# mcu.net
KiCad netlist of a schematic drawn in Altium Designer
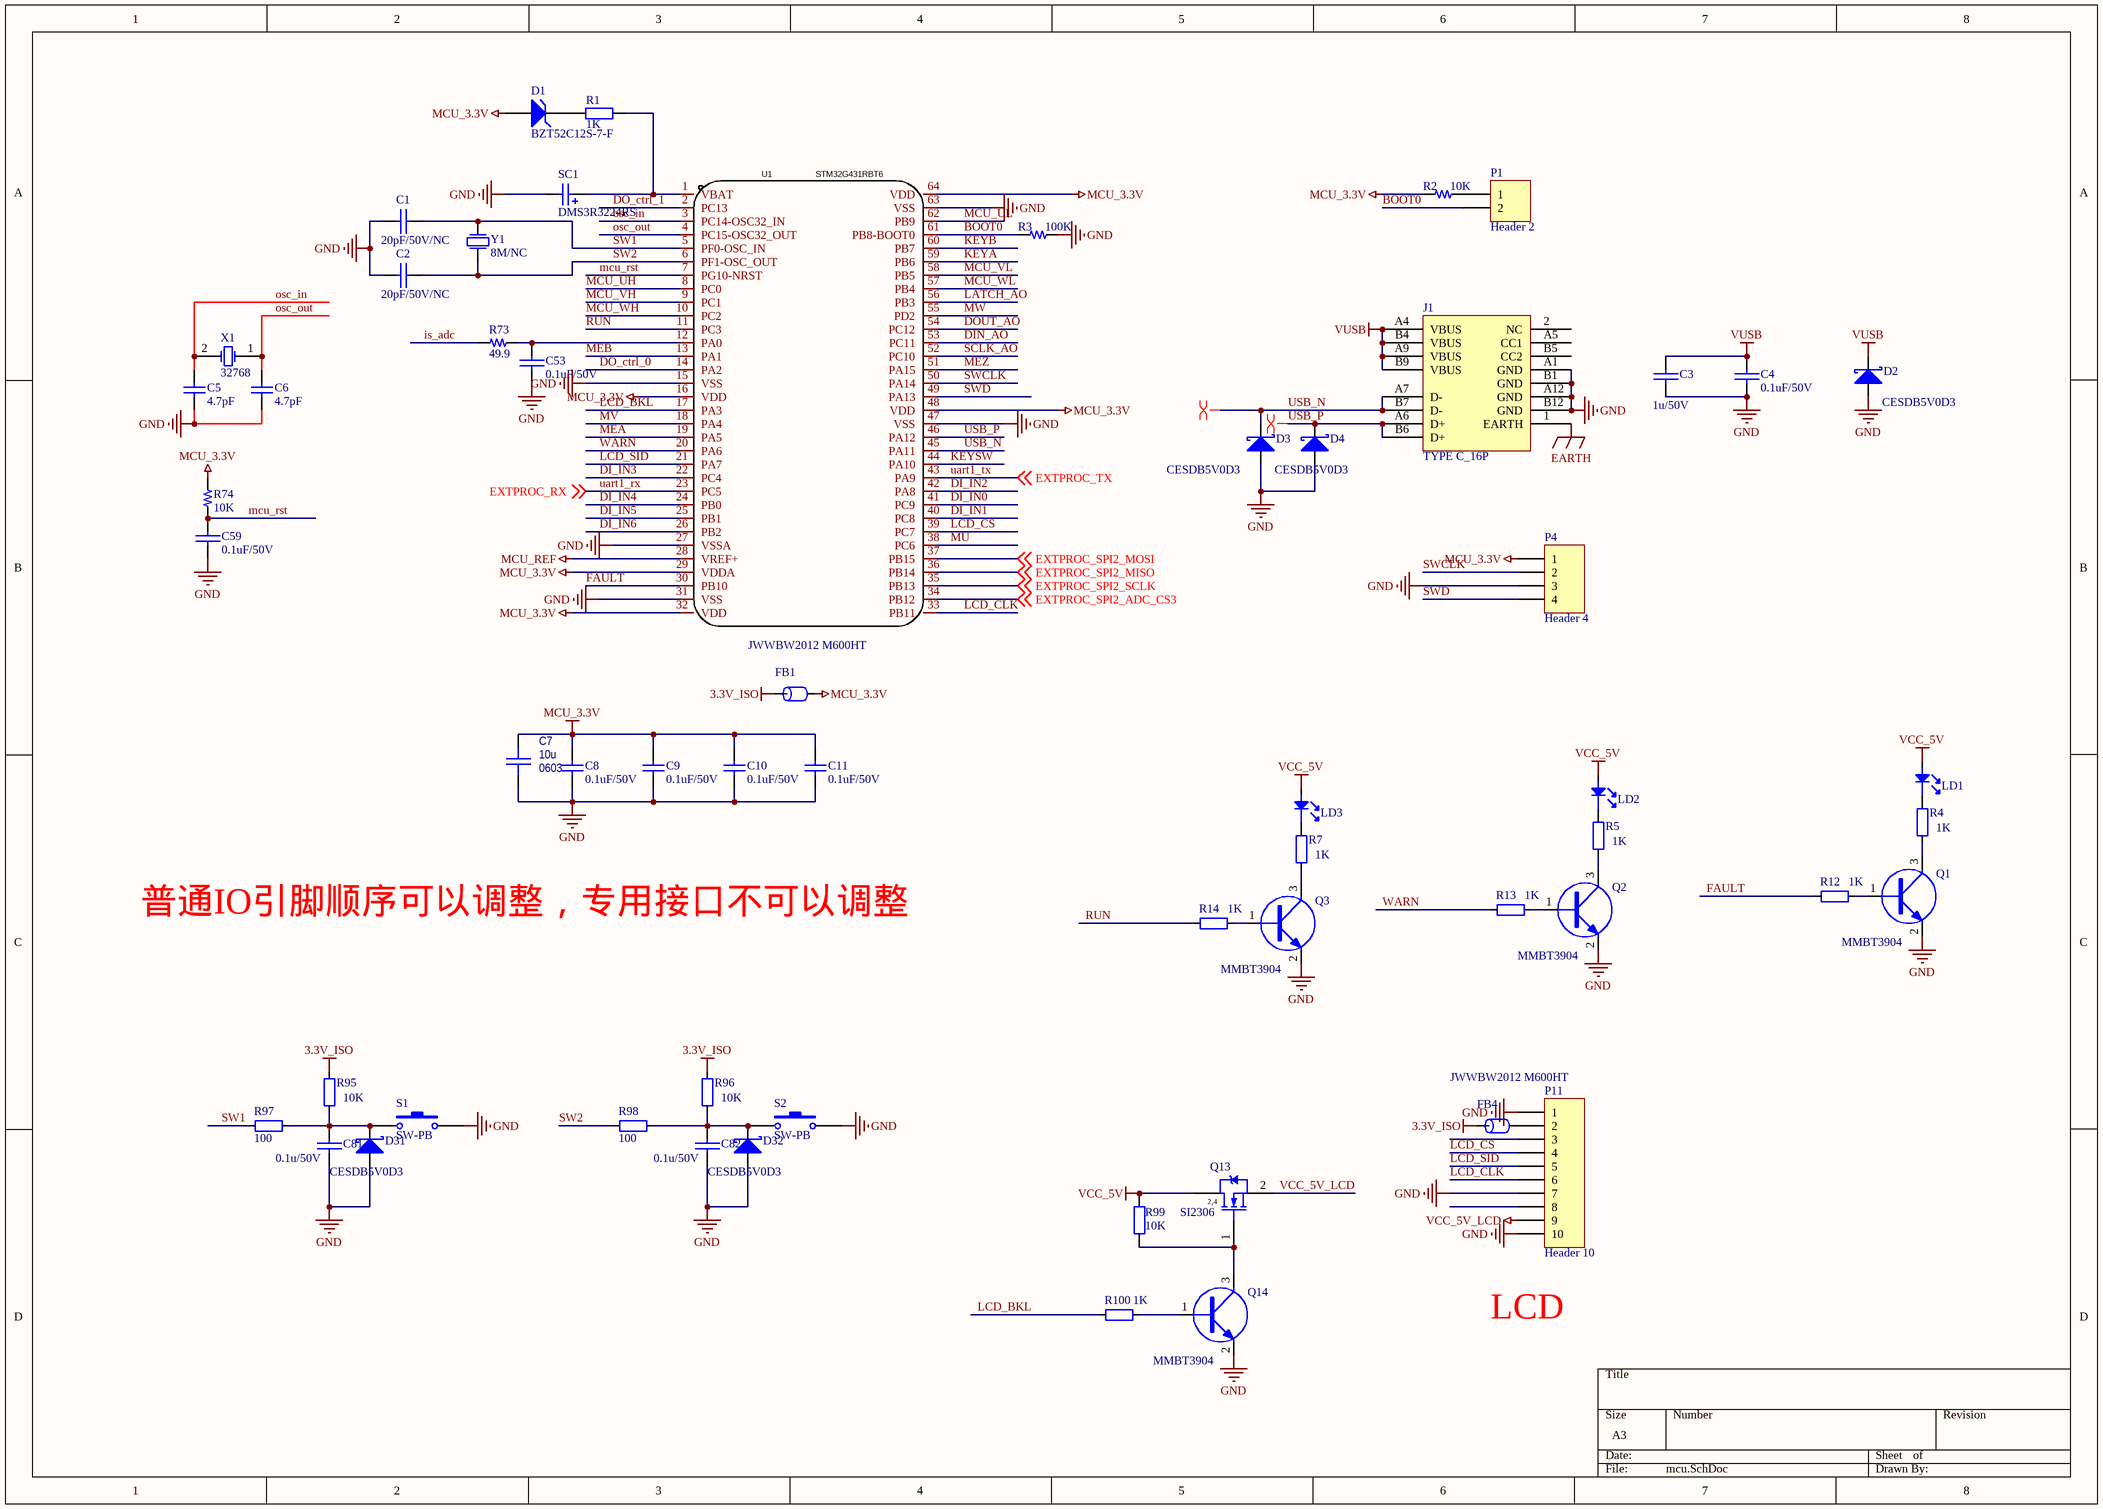
[diagram p0: mcu.SchDoc]

(export (version "E")
  (design (tool "Eeschema 10.0.6"))
  (components
    (comp (ref "C1")
      (value "20pF/50V/NC")
      (footprint "0603C")
      (fields (field (name "Comment") "20pF/25V/NC"))
      (libsource (lib "SM") (part "CAP"))
    )
    (comp (ref "C2")
      (value "20pF/50V/NC")
      (footprint "0603C")
      (fields (field (name "Comment") "20pF/25V/NC"))
      (libsource (lib "SM") (part "CAP"))
    )
    (comp (ref "C3")
      (value "1u/50V")
      (footprint "0603C")
      (fields (field (name "Comment") "1uF/25V"))
      (libsource (lib "SM") (part "CAP"))
    )
    (comp (ref "C4") (value "0.1uF/50V") (footprint "0603C") (libsource (lib "SM") (part "CAP")))
    (comp (ref "C5")
      (value "4.7pF")
      (footprint "0603C")
      (description "Capacitor")
      (fields (field (name "PUBLISHER") "Altium Limited"))
      (libsource (lib "Miscellaneous Devices") (part "Cap"))
    )
    (comp (ref "C6")
      (value "4.7pF")
      (footprint "0603C")
      (description "Capacitor")
      (fields (field (name "PUBLISHER") "Altium Limited"))
      (libsource (lib "Miscellaneous Devices") (part "Cap"))
    )
    (comp (ref "C7")
      (value "10u")
      (footprint "CAPC1608X092N_0603")
      (description "Capacitor, MLCC")
      (fields
        (field (name "MANUFACTURER") "Murata Electronics")
        (field (name "PARTNUMBER") "GRM188R61A106KE69D")
        (field (name "PACKAGE") "0603")
      )
      (libsource (lib "Karl") (part "Capacitor_0603"))
    )
    (comp (ref "C8")
      (value "0.1uF/50V")
      (footprint "0603C")
      (description "Capacitor")
      (fields (field (name "PUBLISHER") "Altium Limited"))
      (libsource (lib "Miscellaneous Devices") (part "Cap"))
    )
    (comp (ref "C9")
      (value "0.1uF/50V")
      (footprint "0603C")
      (description "Capacitor")
      (fields (field (name "PUBLISHER") "Altium Limited"))
      (libsource (lib "Miscellaneous Devices") (part "Cap"))
    )
    (comp (ref "C10")
      (value "0.1uF/50V")
      (footprint "0603C")
      (description "Capacitor")
      (fields (field (name "PUBLISHER") "Altium Limited"))
      (libsource (lib "Miscellaneous Devices") (part "Cap"))
    )
    (comp (ref "C11")
      (value "0.1uF/50V")
      (footprint "0603C")
      (description "Capacitor")
      (fields (field (name "PUBLISHER") "Altium Limited"))
      (libsource (lib "Miscellaneous Devices") (part "Cap"))
    )
    (comp (ref "C53") (value "0.1uF/50V") (footprint "0603C") (libsource (lib "SM") (part "CAP")))
    (comp (ref "C59") (value "0.1uF/50V") (footprint "0603C") (libsource (lib "SM") (part "CAP")))
    (comp (ref "C81")
      (value "0.1u/50V")
      (footprint "0603C")
      (fields (field (name "Comment") "1uF/25V"))
      (libsource (lib "SM") (part "CAP"))
    )
    (comp (ref "C82")
      (value "0.1u/50V")
      (footprint "0603C")
      (fields (field (name "Comment") "1uF/25V"))
      (libsource (lib "SM") (part "CAP"))
    )
    (comp (ref "D1")
      (value "BZT52C12S-7-F")
      (footprint "DIOD-SOD323-2_V")
      (libsource (lib "Bogen") (part "BZT52C12S-7-F"))
    )
    (comp (ref "D2") (value "CESDB5V0D3") (footprint "SOD323") (libsource (lib "*") (part "DIODE S")))
    (comp (ref "D3") (value "CESDB5V0D3") (footprint "SOD323") (libsource (lib "*") (part "DIODE S")))
    (comp (ref "D4") (value "CESDB5V0D3") (footprint "SOD323") (libsource (lib "*") (part "DIODE S")))
    (comp (ref "D31") (value "CESDB5V0D3") (footprint "SOD323") (libsource (lib "*") (part "DIODE S")))
    (comp (ref "D32") (value "CESDB5V0D3") (footprint "SOD323") (libsource (lib "*") (part "DIODE S")))
    (comp (ref "FB1")
      (value "JWWBW2012 M600HT")
      (footprint "0805R")
      (libsource (lib "Schlib_20110825") (part "FB"))
    )
    (comp (ref "FB4")
      (value "JWWBW2012 M600HT")
      (footprint "0805R")
      (libsource (lib "Schlib_20110825") (part "FB"))
    )
    (comp (ref "J1")
      (value "TYPE C_16P")
      (footprint "TYPEC_16P")
      (libsource (lib "Schlib_20110825") (part "TYPE C_16P"))
    )
    (comp (ref "LD1")
      (value "LED_Green_19-217")
      (footprint "0603led")
      (libsource (lib "RC_M_D_00") (part "LED_Green_19-217"))
    )
    (comp (ref "LD2")
      (value "LED_Green_19-217")
      (footprint "0603led")
      (libsource (lib "RC_M_D_00") (part "LED_Green_19-217"))
    )
    (comp (ref "LD3")
      (value "LED_Green_19-217")
      (footprint "0603led")
      (libsource (lib "RC_M_D_00") (part "LED_Green_19-217"))
    )
    (comp (ref "P1")
      (value "Header 2")
      (footprint "HDR1X2")
      (fields (field (name "PUBLISHER") "Altium Limited"))
      (libsource (lib "Miscellaneous Connectors") (part "Header 2"))
    )
    (comp (ref "P4")
      (value "Header 4")
      (footprint "HDR1X4")
      (fields (field (name "PUBLISHER") "Altium Limited"))
      (libsource (lib "Miscellaneous Connectors") (part "Header 4"))
    )
    (comp (ref "P11")
      (value "Header 10")
      (footprint "HDR1X10")
      (description "Header, 10-Pin")
      (fields (field (name "PUBLISHER") "Altium Limited"))
      (libsource (lib "Miscellaneous Connectors") (part "Header 10"))
    )
    (comp (ref "Q1")
      (value "MMBT3904")
      (footprint "SOT23-3")
      (libsource (lib "CenLib") (part "NPN_MMBT3904"))
    )
    (comp (ref "Q2")
      (value "MMBT3904")
      (footprint "SOT23-3")
      (libsource (lib "CenLib") (part "NPN_MMBT3904"))
    )
    (comp (ref "Q3")
      (value "MMBT3904")
      (footprint "SOT23-3")
      (libsource (lib "CenLib") (part "NPN_MMBT3904"))
    )
    (comp (ref "Q13")
      (value "SI2306")
      (footprint "Pcblib_20110825:SOT23-3")
      (description "BUK92150-55A")
      (fields (field (name "PUBLISHER") "Altium Limited"))
      (libsource (lib "Schlib1") (part "BUK92150-55A"))
    )
    (comp (ref "Q14")
      (value "MMBT3904")
      (footprint "SOT23-3")
      (libsource (lib "CenLib") (part "NPN_MMBT3904"))
    )
    (comp (ref "R1") (value "1K") (footprint "0603R") (libsource (lib "MQlibrary") (part "Res0805M")))
    (comp (ref "R2") (value "10K") (footprint "0603R") (libsource (lib "JRJ_1") (part "R")))
    (comp (ref "R3") (value "100K") (footprint "0603R") (libsource (lib "JRJ_1") (part "R")))
    (comp (ref "R4") (value "1K") (footprint "0603r") (libsource (lib "RC_M_D_00") (part "RES0603")))
    (comp (ref "R5") (value "1K") (footprint "0603r") (libsource (lib "RC_M_D_00") (part "RES0603")))
    (comp (ref "R7") (value "1K") (footprint "0603r") (libsource (lib "RC_M_D_00") (part "RES0603")))
    (comp (ref "R12") (value "1K") (footprint "0603r") (libsource (lib "RC_M_D_00") (part "RES0603")))
    (comp (ref "R13") (value "1K") (footprint "0603r") (libsource (lib "RC_M_D_00") (part "RES0603")))
    (comp (ref "R14") (value "1K") (footprint "0603r") (libsource (lib "RC_M_D_00") (part "RES0603")))
    (comp (ref "R73") (value "49.9") (footprint "0603R") (libsource (lib "JRJ_1") (part "R")))
    (comp (ref "R74") (value "10K") (footprint "0603R") (libsource (lib "JRJ_1") (part "R")))
    (comp (ref "R95") (value "10K") (footprint "0603r") (libsource (lib "RC_M_D_00") (part "RES0603")))
    (comp (ref "R96") (value "10K") (footprint "0603r") (libsource (lib "RC_M_D_00") (part "RES0603")))
    (comp (ref "R97") (value "100") (footprint "0603r") (libsource (lib "RC_M_D_00") (part "RES0603")))
    (comp (ref "R98") (value "100") (footprint "0603r") (libsource (lib "RC_M_D_00") (part "RES0603")))
    (comp (ref "R99")
      (value "10K")
      (footprint "Pcblib_20110825:0603R")
      (description "Resistor")
      (fields (field (name "PUBLISHER") "Altium Limited"))
      (libsource (lib "Miscellaneous Devices") (part "Res2"))
    )
    (comp (ref "R100") (value "1K") (footprint "0603r") (libsource (lib "RC_M_D_00") (part "RES0603")))
    (comp (ref "S1")
      (value "SW-PB")
      (footprint "SPST-2")
      (description "Switch")
      (fields (field (name "PUBLISHER") "Altium Limited"))
      (libsource (lib "Miscellaneous Devices") (part "SW-PB"))
    )
    (comp (ref "S2")
      (value "SW-PB")
      (footprint "SPST-2")
      (description "Switch")
      (fields (field (name "PUBLISHER") "Altium Limited"))
      (libsource (lib "Miscellaneous Devices") (part "SW-PB"))
    )
    (comp (ref "SC1")
      (value "DMS3R3224RS")
      (footprint "CAP-TH_DMS3R3224")
      (description "Polarized Capacitor (Axial)")
      (fields (field (name "PUBLISHER") "Altium Limited"))
      (libsource (lib "Miscellaneous Devices") (part "Cap Pol2"))
    )
    (comp (ref "U1")
      (value "STM32G431RBT6")
      (footprint "LQFP-64")
      (fields (field (name "MANUFACTURER") "ST(意法半导体)"))
      (libsource (lib "altium-import") (part "root_0_STM32G431RBT6_"))
    )
    (comp (ref "X1")
      (value "32768")
      (footprint "A")
      (description "Crystal Oscillator")
      (fields (field (name "PUBLISHER") "Altium Limited"))
      (libsource (lib "") (part "XTAL_1"))
    )
    (comp (ref "Y1")
      (value "8M/NC")
      (footprint "CRAY_5032")
      (libsource (lib "Miscellaneous Devices") (part "XTAL"))
    )
  )
  (nets
    (net (code "1") (name "/BOOT0") (class "Default")
      (node (ref "P1") (pin "2") (pinfunction "2_2") (pintype "passive"))
      (node (ref "R3") (pin "1") (pintype "passive"))
      (node (ref "U1") (pin "61") (pinfunction "PB8-BOOT0_61") (pintype "passive"))
    )
    (net (code "2") (name "/DIN_AO") (class "Default")
      (node (ref "U1") (pin "53") (pinfunction "PC11_53") (pintype "passive"))
    )
    (net (code "3") (name "/DI_IN0") (class "Default")
      (node (ref "U1") (pin "41") (pinfunction "PC9_41") (pintype "passive"))
    )
    (net (code "4") (name "/DI_IN1") (class "Default")
      (node (ref "U1") (pin "40") (pinfunction "PC8_40") (pintype "passive"))
    )
    (net (code "5") (name "/DI_IN2") (class "Default")
      (node (ref "U1") (pin "42") (pinfunction "PA8_42") (pintype "passive"))
    )
    (net (code "6") (name "/DI_IN3") (class "Default")
      (node (ref "U1") (pin "22") (pinfunction "PC4_22") (pintype "passive"))
    )
    (net (code "7") (name "/DI_IN4") (class "Default")
      (node (ref "U1") (pin "24") (pinfunction "PB0_24") (pintype "passive"))
    )
    (net (code "8") (name "/DI_IN5") (class "Default")
      (node (ref "U1") (pin "25") (pinfunction "PB1_25") (pintype "passive"))
    )
    (net (code "9") (name "/DI_IN6") (class "Default")
      (node (ref "U1") (pin "26") (pinfunction "PB2_26") (pintype "passive"))
    )
    (net (code "10") (name "/DOUT_AO") (class "Default")
      (node (ref "U1") (pin "54") (pinfunction "PC12_54") (pintype "passive"))
    )
    (net (code "11") (name "/DO_ctrl_0") (class "Default")
      (node (ref "U1") (pin "14") (pinfunction "PA2_14") (pintype "passive"))
    )
    (net (code "12") (name "/DO_ctrl_1") (class "Default")
      (node (ref "U1") (pin "2") (pinfunction "PC13_2") (pintype "passive"))
    )
    (net (code "13") (name "/FAULT") (class "Default")
      (node (ref "R12") (pin "1") (pinfunction "1_1") (pintype "passive"))
      (node (ref "U1") (pin "30") (pinfunction "PB10_30") (pintype "passive"))
    )
    (net (code "14") (name "/KEYA") (class "Default")
      (node (ref "U1") (pin "59") (pinfunction "PB6_59") (pintype "passive"))
    )
    (net (code "15") (name "/KEYB") (class "Default")
      (node (ref "U1") (pin "60") (pinfunction "PB7_60") (pintype "passive"))
    )
    (net (code "16") (name "/KEYSW") (class "Default")
      (node (ref "U1") (pin "44") (pinfunction "PA10_44") (pintype "passive"))
    )
    (net (code "17") (name "/LATCH_AO") (class "Default")
      (node (ref "U1") (pin "56") (pinfunction "PB3_56") (pintype "passive"))
    )
    (net (code "18") (name "/LCD_BKL") (class "Default")
      (node (ref "R100") (pin "1") (pinfunction "1_1") (pintype "passive"))
      (node (ref "U1") (pin "17") (pinfunction "PA3_17") (pintype "passive"))
    )
    (net (code "19") (name "/LCD_CLK") (class "Default")
      (node (ref "P11") (pin "6") (pinfunction "6_6") (pintype "passive"))
      (node (ref "U1") (pin "33") (pinfunction "PB11_33") (pintype "passive"))
    )
    (net (code "20") (name "/LCD_CS") (class "Default")
      (node (ref "P11") (pin "4") (pinfunction "4_4") (pintype "passive"))
      (node (ref "U1") (pin "39") (pinfunction "PC7_39") (pintype "passive"))
    )
    (net (code "21") (name "/LCD_SID") (class "Default")
      (node (ref "P11") (pin "5") (pinfunction "5_5") (pintype "passive"))
      (node (ref "U1") (pin "21") (pinfunction "PA7_21") (pintype "passive"))
    )
    (net (code "22") (name "/MCU_UH") (class "Default")
      (node (ref "U1") (pin "8") (pinfunction "PC0_8") (pintype "passive"))
    )
    (net (code "23") (name "/MCU_UL") (class "Default")
      (node (ref "U1") (pin "62") (pinfunction "PB9_62") (pintype "passive"))
    )
    (net (code "24") (name "/MCU_VH") (class "Default")
      (node (ref "U1") (pin "9") (pinfunction "PC1_9") (pintype "passive"))
    )
    (net (code "25") (name "/MCU_VL") (class "Default")
      (node (ref "U1") (pin "58") (pinfunction "PB5_58") (pintype "passive"))
    )
    (net (code "26") (name "/MCU_WH") (class "Default")
      (node (ref "U1") (pin "10") (pinfunction "PC2_10") (pintype "passive"))
    )
    (net (code "27") (name "/MCU_WL") (class "Default")
      (node (ref "U1") (pin "57") (pinfunction "PB4_57") (pintype "passive"))
    )
    (net (code "28") (name "/MEA") (class "Default")
      (node (ref "U1") (pin "19") (pinfunction "PA5_19") (pintype "passive"))
    )
    (net (code "29") (name "/MEB") (class "Default")
      (node (ref "U1") (pin "13") (pinfunction "PA1_13") (pintype "passive"))
    )
    (net (code "30") (name "/MEZ") (class "Default")
      (node (ref "U1") (pin "51") (pinfunction "PA15_51") (pintype "passive"))
    )
    (net (code "31") (name "/MU") (class "Default")
      (node (ref "U1") (pin "38") (pinfunction "PC6_38") (pintype "passive"))
    )
    (net (code "32") (name "/MV") (class "Default")
      (node (ref "U1") (pin "18") (pinfunction "PA4_18") (pintype "passive"))
    )
    (net (code "33") (name "/MW") (class "Default")
      (node (ref "U1") (pin "55") (pinfunction "PD2_55") (pintype "passive"))
    )
    (net (code "34") (name "/RUN") (class "Default")
      (node (ref "R14") (pin "1") (pinfunction "1_1") (pintype "passive"))
      (node (ref "U1") (pin "11") (pinfunction "PC3_11") (pintype "passive"))
    )
    (net (code "35") (name "/SCLK_AO") (class "Default")
      (node (ref "U1") (pin "52") (pinfunction "PC10_52") (pintype "passive"))
    )
    (net (code "36") (name "/SW1") (class "Default")
      (node (ref "C1") (pin "1") (pinfunction "1_1") (pintype "passive"))
      (node (ref "R97") (pin "1") (pinfunction "1_1") (pintype "passive"))
      (node (ref "U1") (pin "5") (pinfunction "PF0-OSC_IN_5") (pintype "passive"))
      (node (ref "Y1") (pin "1") (pinfunction "P1_1") (pintype "passive"))
    )
    (net (code "37") (name "/SW2") (class "Default")
      (node (ref "C2") (pin "1") (pinfunction "1_1") (pintype "passive"))
      (node (ref "R98") (pin "1") (pinfunction "1_1") (pintype "passive"))
      (node (ref "U1") (pin "6") (pinfunction "PF1-OSC_OUT_6") (pintype "passive"))
      (node (ref "Y1") (pin "2") (pinfunction "P2_2") (pintype "passive"))
    )
    (net (code "38") (name "/SWCLK") (class "Default")
      (node (ref "P4") (pin "2") (pinfunction "2_2") (pintype "passive"))
      (node (ref "U1") (pin "50") (pinfunction "PA14_50") (pintype "passive"))
    )
    (net (code "39") (name "/SWD") (class "Default")
      (node (ref "P4") (pin "4") (pinfunction "4_4") (pintype "passive"))
      (node (ref "U1") (pin "49") (pinfunction "PA13_49") (pintype "passive"))
    )
    (net (code "40") (name "/USB_N") (class "Default")
      (node (ref "D3") (pin "2") (pinfunction "K_2") (pintype "passive"))
      (node (ref "J1") (pin "A7") (pinfunction "D-_A7") (pintype "passive"))
      (node (ref "J1") (pin "B7") (pinfunction "D-_B7") (pintype "passive"))
      (node (ref "U1") (pin "45") (pinfunction "PA11_45") (pintype "passive"))
    )
    (net (code "41") (name "/USB_P") (class "Default")
      (node (ref "D4") (pin "2") (pinfunction "K_2") (pintype "passive"))
      (node (ref "J1") (pin "A6") (pinfunction "D+_A6") (pintype "passive"))
      (node (ref "J1") (pin "B6") (pinfunction "D+_B6") (pintype "passive"))
      (node (ref "U1") (pin "46") (pinfunction "PA12_46") (pintype "passive"))
    )
    (net (code "42") (name "/WARN") (class "Default")
      (node (ref "R13") (pin "1") (pinfunction "1_1") (pintype "passive"))
      (node (ref "U1") (pin "20") (pinfunction "PA6_20") (pintype "passive"))
    )
    (net (code "43") (name "/is_adc") (class "Default") (node (ref "R73") (pin "1") (pintype "passive")))
    (net (code "44") (name "/mcu_rst") (class "Default")
      (node (ref "C59") (pin "2") (pinfunction "2_2") (pintype "passive"))
      (node (ref "R74") (pin "2") (pintype "passive"))
      (node (ref "U1") (pin "7") (pinfunction "PG10-NRST_7") (pintype "passive"))
    )
    (net (code "45") (name "/osc_in") (class "Default")
      (node (ref "C5") (pin "1") (pinfunction "1_1") (pintype "passive"))
      (node (ref "U1") (pin "3") (pinfunction "PC14-OSC32_IN_3") (pintype "passive"))
      (node (ref "X1") (pin "2") (pinfunction "OSC2_2") (pintype "passive"))
    )
    (net (code "46") (name "/osc_out") (class "Default")
      (node (ref "C6") (pin "1") (pinfunction "1_1") (pintype "passive"))
      (node (ref "U1") (pin "4") (pinfunction "PC15-OSC32_OUT_4") (pintype "passive"))
      (node (ref "X1") (pin "1") (pinfunction "OSC1_1") (pintype "passive"))
    )
    (net (code "47") (name "3.3V_ISO") (class "Default")
      (node (ref "FB1") (pin "1") (pintype "passive"))
      (node (ref "FB4") (pin "1") (pintype "passive"))
      (node (ref "R95") (pin "1") (pinfunction "1_1") (pintype "passive"))
      (node (ref "R96") (pin "1") (pinfunction "1_1") (pintype "passive"))
    )
    (net (code "48") (name "EARTH") (class "Default")
      (node (ref "J1") (pin "1") (pinfunction "EARTH_1") (pintype "passive"))
    )
    (net (code "49") (name "EXTPROC_RX") (class "Default")
      (node (ref "U1") (pin "23") (pinfunction "PC5_23") (pintype "passive"))
    )
    (net (code "50") (name "EXTPROC_SPI2_ADC_CS3") (class "Default")
      (node (ref "U1") (pin "34") (pinfunction "PB12_34") (pintype "passive"))
    )
    (net (code "51") (name "EXTPROC_SPI2_MISO") (class "Default")
      (node (ref "U1") (pin "36") (pinfunction "PB14_36") (pintype "passive"))
    )
    (net (code "52") (name "EXTPROC_SPI2_MOSI") (class "Default")
      (node (ref "U1") (pin "37") (pinfunction "PB15_37") (pintype "passive"))
    )
    (net (code "53") (name "EXTPROC_SPI2_SCLK") (class "Default")
      (node (ref "U1") (pin "35") (pinfunction "PB13_35") (pintype "passive"))
    )
    (net (code "54") (name "EXTPROC_TX") (class "Default")
      (node (ref "U1") (pin "43") (pinfunction "PA9_43") (pintype "passive"))
    )
    (net (code "55") (name "GND") (class "Default")
      (node (ref "C1") (pin "2") (pinfunction "2_2") (pintype "passive"))
      (node (ref "C10") (pin "1") (pinfunction "1_1") (pintype "passive"))
      (node (ref "C11") (pin "1") (pinfunction "1_1") (pintype "passive"))
      (node (ref "C2") (pin "2") (pinfunction "2_2") (pintype "passive"))
      (node (ref "C3") (pin "1") (pinfunction "1_1") (pintype "passive"))
      (node (ref "C4") (pin "1") (pinfunction "1_1") (pintype "passive"))
      (node (ref "C5") (pin "2") (pinfunction "2_2") (pintype "passive"))
      (node (ref "C53") (pin "1") (pinfunction "1_1") (pintype "passive"))
      (node (ref "C59") (pin "1") (pinfunction "1_1") (pintype "passive"))
      (node (ref "C6") (pin "2") (pinfunction "2_2") (pintype "passive"))
      (node (ref "C7") (pin "2") (pinfunction "2_2") (pintype "passive"))
      (node (ref "C8") (pin "1") (pinfunction "1_1") (pintype "passive"))
      (node (ref "C81") (pin "1") (pinfunction "1_1") (pintype "passive"))
      (node (ref "C82") (pin "1") (pinfunction "1_1") (pintype "passive"))
      (node (ref "C9") (pin "1") (pinfunction "1_1") (pintype "passive"))
      (node (ref "D2") (pin "1") (pinfunction "A_1") (pintype "passive"))
      (node (ref "D3") (pin "1") (pinfunction "A_1") (pintype "passive"))
      (node (ref "D31") (pin "1") (pinfunction "A_1") (pintype "passive"))
      (node (ref "D32") (pin "1") (pinfunction "A_1") (pintype "passive"))
      (node (ref "D4") (pin "1") (pinfunction "A_1") (pintype "passive"))
      (node (ref "J1") (pin "A1") (pinfunction "GND_A1") (pintype "passive"))
      (node (ref "J1") (pin "A12") (pinfunction "GND_A12") (pintype "passive"))
      (node (ref "J1") (pin "B1") (pinfunction "GND_B1") (pintype "passive"))
      (node (ref "J1") (pin "B12") (pinfunction "GND_B12") (pintype "passive"))
      (node (ref "P11") (pin "1") (pinfunction "1_1") (pintype "passive"))
      (node (ref "P11") (pin "10") (pinfunction "10_10") (pintype "passive"))
      (node (ref "P11") (pin "7") (pinfunction "7_7") (pintype "passive"))
      (node (ref "P4") (pin "3") (pinfunction "3_3") (pintype "passive"))
      (node (ref "Q1") (pin "2") (pinfunction "E_2") (pintype "passive"))
      (node (ref "Q14") (pin "2") (pinfunction "E_2") (pintype "passive"))
      (node (ref "Q2") (pin "2") (pinfunction "E_2") (pintype "passive"))
      (node (ref "Q3") (pin "2") (pinfunction "E_2") (pintype "passive"))
      (node (ref "R3") (pin "2") (pintype "passive"))
      (node (ref "S1") (pin "2") (pinfunction "2_2") (pintype "passive"))
      (node (ref "S2") (pin "2") (pinfunction "2_2") (pintype "passive"))
      (node (ref "SC1") (pin "2") (pinfunction "2_2") (pintype "passive"))
      (node (ref "U1") (pin "15") (pinfunction "VSS_15") (pintype "passive"))
      (node (ref "U1") (pin "27") (pinfunction "VSSA_27") (pintype "passive"))
      (node (ref "U1") (pin "31") (pinfunction "VSS_31") (pintype "passive"))
      (node (ref "U1") (pin "47") (pinfunction "VSS_47") (pintype "passive"))
      (node (ref "U1") (pin "63") (pinfunction "VSS_63") (pintype "passive"))
    )
    (net (code "56") (name "MCU_3.3V") (class "Default")
      (node (ref "C10") (pin "2") (pinfunction "2_2") (pintype "passive"))
      (node (ref "C11") (pin "2") (pinfunction "2_2") (pintype "passive"))
      (node (ref "C7") (pin "1") (pinfunction "1_1") (pintype "passive"))
      (node (ref "C8") (pin "2") (pinfunction "2_2") (pintype "passive"))
      (node (ref "C9") (pin "2") (pinfunction "2_2") (pintype "passive"))
      (node (ref "D1") (pin "1") (pinfunction "A_1") (pintype "passive"))
      (node (ref "FB1") (pin "2") (pintype "passive"))
      (node (ref "P4") (pin "1") (pinfunction "1_1") (pintype "passive"))
      (node (ref "R2") (pin "1") (pintype "passive"))
      (node (ref "R74") (pin "1") (pintype "passive"))
      (node (ref "U1") (pin "16") (pinfunction "VDD_16") (pintype "passive"))
      (node (ref "U1") (pin "29") (pinfunction "VDDA_29") (pintype "passive"))
      (node (ref "U1") (pin "32") (pinfunction "VDD_32") (pintype "passive"))
      (node (ref "U1") (pin "48") (pinfunction "VDD_48") (pintype "passive"))
      (node (ref "U1") (pin "64") (pinfunction "VDD_64") (pintype "passive"))
    )
    (net (code "57") (name "MCU_REF") (class "Default")
      (node (ref "U1") (pin "28") (pinfunction "VREF+_28") (pintype "passive"))
    )
    (net (code "58") (name "Net-(D1-K)") (class "Default")
      (node (ref "D1") (pin "2") (pinfunction "K_2") (pintype "passive"))
      (node (ref "R1") (pin "1") (pinfunction "1_1") (pintype "passive"))
    )
    (net (code "59") (name "Net-(D31-K)") (class "Default")
      (node (ref "C81") (pin "2") (pinfunction "2_2") (pintype "passive"))
      (node (ref "D31") (pin "2") (pinfunction "K_2") (pintype "passive"))
      (node (ref "R95") (pin "2") (pinfunction "2_2") (pintype "passive"))
      (node (ref "R97") (pin "2") (pinfunction "2_2") (pintype "passive"))
      (node (ref "S1") (pin "1") (pinfunction "1_1") (pintype "passive"))
    )
    (net (code "60") (name "Net-(D32-K)") (class "Default")
      (node (ref "C82") (pin "2") (pinfunction "2_2") (pintype "passive"))
      (node (ref "D32") (pin "2") (pinfunction "K_2") (pintype "passive"))
      (node (ref "R96") (pin "2") (pinfunction "2_2") (pintype "passive"))
      (node (ref "R98") (pin "2") (pinfunction "2_2") (pintype "passive"))
      (node (ref "S2") (pin "1") (pinfunction "1_1") (pintype "passive"))
    )
    (net (code "61") (name "Net-(FB4-Pad2)") (class "Default")
      (node (ref "FB4") (pin "2") (pintype "passive"))
      (node (ref "P11") (pin "2") (pinfunction "2_2") (pintype "passive"))
    )
    (net (code "62") (name "Net-(LD1-Pad2)") (class "Default")
      (node (ref "LD1") (pin "2") (pinfunction "2_2") (pintype "passive"))
      (node (ref "R4") (pin "1") (pinfunction "1_1") (pintype "passive"))
    )
    (net (code "63") (name "Net-(LD2-Pad2)") (class "Default")
      (node (ref "LD2") (pin "2") (pinfunction "2_2") (pintype "passive"))
      (node (ref "R5") (pin "1") (pinfunction "1_1") (pintype "passive"))
    )
    (net (code "64") (name "Net-(LD3-Pad2)") (class "Default")
      (node (ref "LD3") (pin "2") (pinfunction "2_2") (pintype "passive"))
      (node (ref "R7") (pin "1") (pinfunction "1_1") (pintype "passive"))
    )
    (net (code "65") (name "Net-(P1-Pad1)") (class "Default")
      (node (ref "P1") (pin "1") (pinfunction "1_1") (pintype "passive"))
      (node (ref "R2") (pin "2") (pintype "passive"))
    )
    (net (code "66") (name "Net-(Q1-B)") (class "Default")
      (node (ref "Q1") (pin "1") (pinfunction "B_1") (pintype "passive"))
      (node (ref "R12") (pin "2") (pinfunction "2_2") (pintype "passive"))
    )
    (net (code "67") (name "Net-(Q1-C)") (class "Default")
      (node (ref "Q1") (pin "3") (pinfunction "C_3") (pintype "passive"))
      (node (ref "R4") (pin "2") (pinfunction "2_2") (pintype "passive"))
    )
    (net (code "68") (name "Net-(Q2-B)") (class "Default")
      (node (ref "Q2") (pin "1") (pinfunction "B_1") (pintype "passive"))
      (node (ref "R13") (pin "2") (pinfunction "2_2") (pintype "passive"))
    )
    (net (code "69") (name "Net-(Q2-C)") (class "Default")
      (node (ref "Q2") (pin "3") (pinfunction "C_3") (pintype "passive"))
      (node (ref "R5") (pin "2") (pinfunction "2_2") (pintype "passive"))
    )
    (net (code "70") (name "Net-(Q3-B)") (class "Default")
      (node (ref "Q3") (pin "1") (pinfunction "B_1") (pintype "passive"))
      (node (ref "R14") (pin "2") (pinfunction "2_2") (pintype "passive"))
    )
    (net (code "71") (name "Net-(Q3-C)") (class "Default")
      (node (ref "Q3") (pin "3") (pinfunction "C_3") (pintype "passive"))
      (node (ref "R7") (pin "2") (pinfunction "2_2") (pintype "passive"))
    )
    (net (code "72") (name "Net-(Q13-G)") (class "Default")
      (node (ref "Q13") (pin "1") (pinfunction "G_1") (pintype "passive"))
      (node (ref "Q14") (pin "3") (pinfunction "C_3") (pintype "passive"))
      (node (ref "R99") (pin "1") (pinfunction "1_1") (pintype "passive"))
    )
    (net (code "73") (name "Net-(Q14-B)") (class "Default")
      (node (ref "Q14") (pin "1") (pinfunction "B_1") (pintype "passive"))
      (node (ref "R100") (pin "2") (pinfunction "2_2") (pintype "passive"))
    )
    (net (code "74") (name "Net-(U1-PA0)") (class "Default")
      (node (ref "C53") (pin "2") (pinfunction "2_2") (pintype "passive"))
      (node (ref "R73") (pin "2") (pintype "passive"))
      (node (ref "U1") (pin "12") (pinfunction "PA0_12") (pintype "passive"))
    )
    (net (code "75") (name "Net-(U1-VBAT)") (class "Default")
      (node (ref "R1") (pin "2") (pinfunction "2_2") (pintype "passive"))
      (node (ref "SC1") (pin "1") (pinfunction "1_1") (pintype "passive"))
      (node (ref "U1") (pin "1") (pinfunction "VBAT_1") (pintype "passive"))
    )
    (net (code "76") (name "VCC_5V") (class "Default")
      (node (ref "LD1") (pin "1") (pinfunction "1_1") (pintype "passive"))
      (node (ref "LD2") (pin "1") (pinfunction "1_1") (pintype "passive"))
      (node (ref "LD3") (pin "1") (pinfunction "1_1") (pintype "passive"))
      (node (ref "Q13") (pin "3") (pinfunction "D_3") (pintype "passive"))
      (node (ref "R99") (pin "2") (pinfunction "2_2") (pintype "passive"))
    )
    (net (code "77") (name "VCC_5V_LCD") (class "Default")
      (node (ref "P11") (pin "9") (pinfunction "9_9") (pintype "passive"))
      (node (ref "Q13") (pin "2") (pinfunction "S_2") (pintype "passive"))
    )
    (net (code "78") (name "VUSB") (class "Default")
      (node (ref "C3") (pin "2") (pinfunction "2_2") (pintype "passive"))
      (node (ref "C4") (pin "2") (pinfunction "2_2") (pintype "passive"))
      (node (ref "D2") (pin "2") (pinfunction "K_2") (pintype "passive"))
      (node (ref "J1") (pin "A4") (pinfunction "VBUS_A4") (pintype "passive"))
      (node (ref "J1") (pin "A9") (pinfunction "VBUS_A9") (pintype "passive"))
      (node (ref "J1") (pin "B4") (pinfunction "VBUS_B4") (pintype "passive"))
      (node (ref "J1") (pin "B9") (pinfunction "VBUS_B9") (pintype "passive"))
    )
    (net (code "79") (name "unconnected-(J1-CC1-PadA5)") (class "Default")
      (node (ref "J1") (pin "A5") (pinfunction "CC1_A5") (pintype "passive"))
    )
    (net (code "80") (name "unconnected-(J1-CC2-PadB5)") (class "Default")
      (node (ref "J1") (pin "B5") (pinfunction "CC2_B5") (pintype "passive"))
    )
    (net (code "81") (name "unconnected-(J1-NC-Pad2)") (class "Default")
      (node (ref "J1") (pin "2") (pinfunction "NC_2") (pintype "passive"))
    )
    (net (code "82") (name "unconnected-(P11-Pad3)") (class "Default")
      (node (ref "P11") (pin "3") (pinfunction "3_3") (pintype "passive"))
    )
    (net (code "83") (name "unconnected-(P11-Pad8)") (class "Default")
      (node (ref "P11") (pin "8") (pinfunction "8_8") (pintype "passive"))
    )
  )
)
